# Encoder.net
KiCad netlist of a schematic drawn in Altium Designer
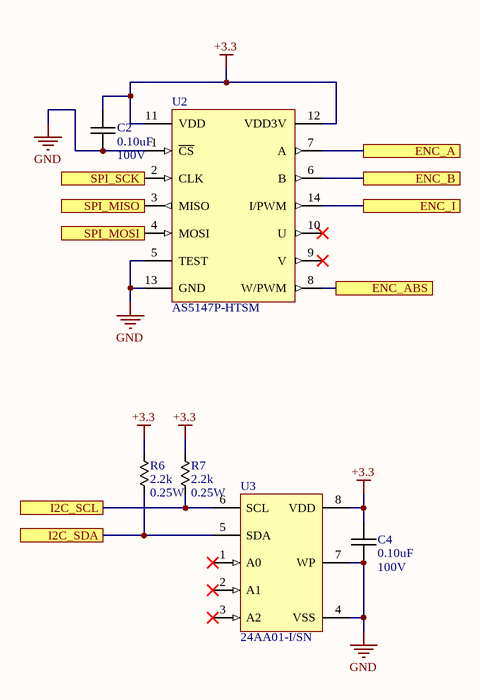
[diagram p0: Encoder.SchDoc]

(export (version "E")
  (design (tool "Eeschema 10.0.6"))
  (components
    (comp (ref "C2")
      (value "cap_single_np")
      (footprint "chip_0805")
      (description "CAP, 0.10uF, 10%, 100V, X7R, 0805")
      (fields
        (field (name "TOLERANCE") "10%")
        (field (name "CAPACITANCE") "0.10uF")
        (field (name "VOLTAGE RATING") "100V")
        (field (name "PART NUMBER") "CAP-00073")
      )
      (libsource (lib "Capacitors") (part "cap_single_np"))
    )
    (comp (ref "C4")
      (value "cap_single_np")
      (footprint "chip_0805")
      (description "CAP, 0.10uF, 10%, 100V, X7R, 0805")
      (fields
        (field (name "TOLERANCE") "10%")
        (field (name "CAPACITANCE") "0.10uF")
        (field (name "VOLTAGE RATING") "100V")
        (field (name "PART NUMBER") "CAP-00073")
      )
      (libsource (lib "Capacitors") (part "cap_single_np"))
    )
    (comp (ref "R6")
      (value "res_single")
      (footprint "chip_0603")
      (description "RES SMD 2.2K OHM 1% 1/4W 0603")
      (fields
        (field (name "TOLERANCE") "1%")
        (field (name "RESISTANCE") "2.2k")
        (field (name "POWER RATING") "0.25W")
        (field (name "PART NUMBER") "RES-00365")
      )
      (libsource (lib "Resistors") (part "res_single"))
    )
    (comp (ref "R7")
      (value "res_single")
      (footprint "chip_0603")
      (description "RES SMD 2.2K OHM 1% 1/4W 0603")
      (fields
        (field (name "TOLERANCE") "1%")
        (field (name "RESISTANCE") "2.2k")
        (field (name "POWER RATING") "0.25W")
        (field (name "PART NUMBER") "RES-00365")
      )
      (libsource (lib "Resistors") (part "res_single"))
    )
    (comp (ref "U2")
      (value "AS5147P-HTSM")
      (footprint "TSSOP-14_0")
      (description "IC, 14-bit On-Axis Magnetic Rotary Position Sensor, Incremental, TSSOP-14")
      (fields (field (name "PART NUMBER") "MISC-00046") (field (name "MANUFACTURER") "AMS"))
      (libsource (lib "Misc") (part "AS5147"))
    )
    (comp (ref "U3")
      (value "24AA01")
      (footprint "SO-8")
      (description "EEPROM, 1K-bit, I2C, 400kHz, 24AA01, 8-SOIC")
      (fields
        (field (name "MANUFACTURER PN") "24AA01-I/SN")
        (field (name "PART NUMBER") "LOGIC-00028")
        (field (name "MANUFACTURER") "Microchip")
      )
      (libsource (lib "Logic") (part "24AA01"))
    )
  )
  (nets
    (net (code "1") (name "+3.3") (class "Default")
      (node (ref "C2") (pin "1") (pinfunction "1_1") (pintype "passive"))
      (node (ref "C4") (pin "1") (pinfunction "1_1") (pintype "passive"))
      (node (ref "R6") (pin "1") (pinfunction "1_1") (pintype "passive"))
      (node (ref "R7") (pin "1") (pinfunction "1_1") (pintype "passive"))
      (node (ref "U2") (pin "11") (pinfunction "VDD_11") (pintype "power_in"))
      (node (ref "U2") (pin "12") (pinfunction "VDD3V_12") (pintype "power_in"))
      (node (ref "U3") (pin "8") (pinfunction "VDD_8") (pintype "power_in"))
    )
    (net (code "2") (name "/ENC_A") (class "Default")
      (node (ref "U2") (pin "7") (pinfunction "A_7") (pintype "output"))
    )
    (net (code "3") (name "/ENC_ABS") (class "Default")
      (node (ref "U2") (pin "8") (pinfunction "W/PWM_8") (pintype "output"))
    )
    (net (code "4") (name "/ENC_B") (class "Default")
      (node (ref "U2") (pin "6") (pinfunction "B_6") (pintype "output"))
    )
    (net (code "5") (name "/ENC_I") (class "Default")
      (node (ref "U2") (pin "14") (pinfunction "I/PWM_14") (pintype "output"))
    )
    (net (code "6") (name "/I2C_SCL") (class "Default")
      (node (ref "R7") (pin "2") (pinfunction "2_2") (pintype "passive"))
      (node (ref "U3") (pin "6") (pinfunction "SCL_6") (pintype "open_collector"))
    )
    (net (code "7") (name "/I2C_SDA") (class "Default")
      (node (ref "R6") (pin "2") (pinfunction "2_2") (pintype "passive"))
      (node (ref "U3") (pin "5") (pinfunction "SDA_5") (pintype "open_collector"))
    )
    (net (code "8") (name "/SPI_MISO") (class "Default")
      (node (ref "U2") (pin "3") (pinfunction "MISO_3") (pintype "output"))
    )
    (net (code "9") (name "/SPI_MOSI") (class "Default")
      (node (ref "U2") (pin "4") (pinfunction "MOSI_4") (pintype "input"))
    )
    (net (code "10") (name "/SPI_SCK") (class "Default")
      (node (ref "U2") (pin "2") (pinfunction "CLK_2") (pintype "input"))
    )
    (net (code "11") (name "GND") (class "Default")
      (node (ref "C2") (pin "2") (pinfunction "2_2") (pintype "passive"))
      (node (ref "C4") (pin "2") (pinfunction "2_2") (pintype "passive"))
      (node (ref "U2") (pin "1") (pinfunction "~{CS}_1") (pintype "input"))
      (node (ref "U2") (pin "13") (pinfunction "GND_13") (pintype "power_in"))
      (node (ref "U2") (pin "5") (pinfunction "TEST_5") (pintype "passive"))
      (node (ref "U3") (pin "4") (pinfunction "VSS_4") (pintype "power_in"))
      (node (ref "U3") (pin "7") (pinfunction "WP_7") (pintype "passive"))
    )
    (net (code "12") (name "unconnected-(U2-U-Pad10)") (class "Default")
      (node (ref "U2") (pin "10") (pinfunction "U_10") (pintype "output+no_connect"))
    )
    (net (code "13") (name "unconnected-(U2-V-Pad9)") (class "Default")
      (node (ref "U2") (pin "9") (pinfunction "V_9") (pintype "output+no_connect"))
    )
    (net (code "14") (name "unconnected-(U3-A0-Pad1)") (class "Default")
      (node (ref "U3") (pin "1") (pinfunction "A0_1") (pintype "input+no_connect"))
    )
    (net (code "15") (name "unconnected-(U3-A1-Pad2)") (class "Default")
      (node (ref "U3") (pin "2") (pinfunction "A1_2") (pintype "input+no_connect"))
    )
    (net (code "16") (name "unconnected-(U3-A2-Pad3)") (class "Default")
      (node (ref "U3") (pin "3") (pinfunction "A2_3") (pintype "input+no_connect"))
    )
  )
)
